# design.net
KiCad netlist of a schematic drawn in Altium Designer
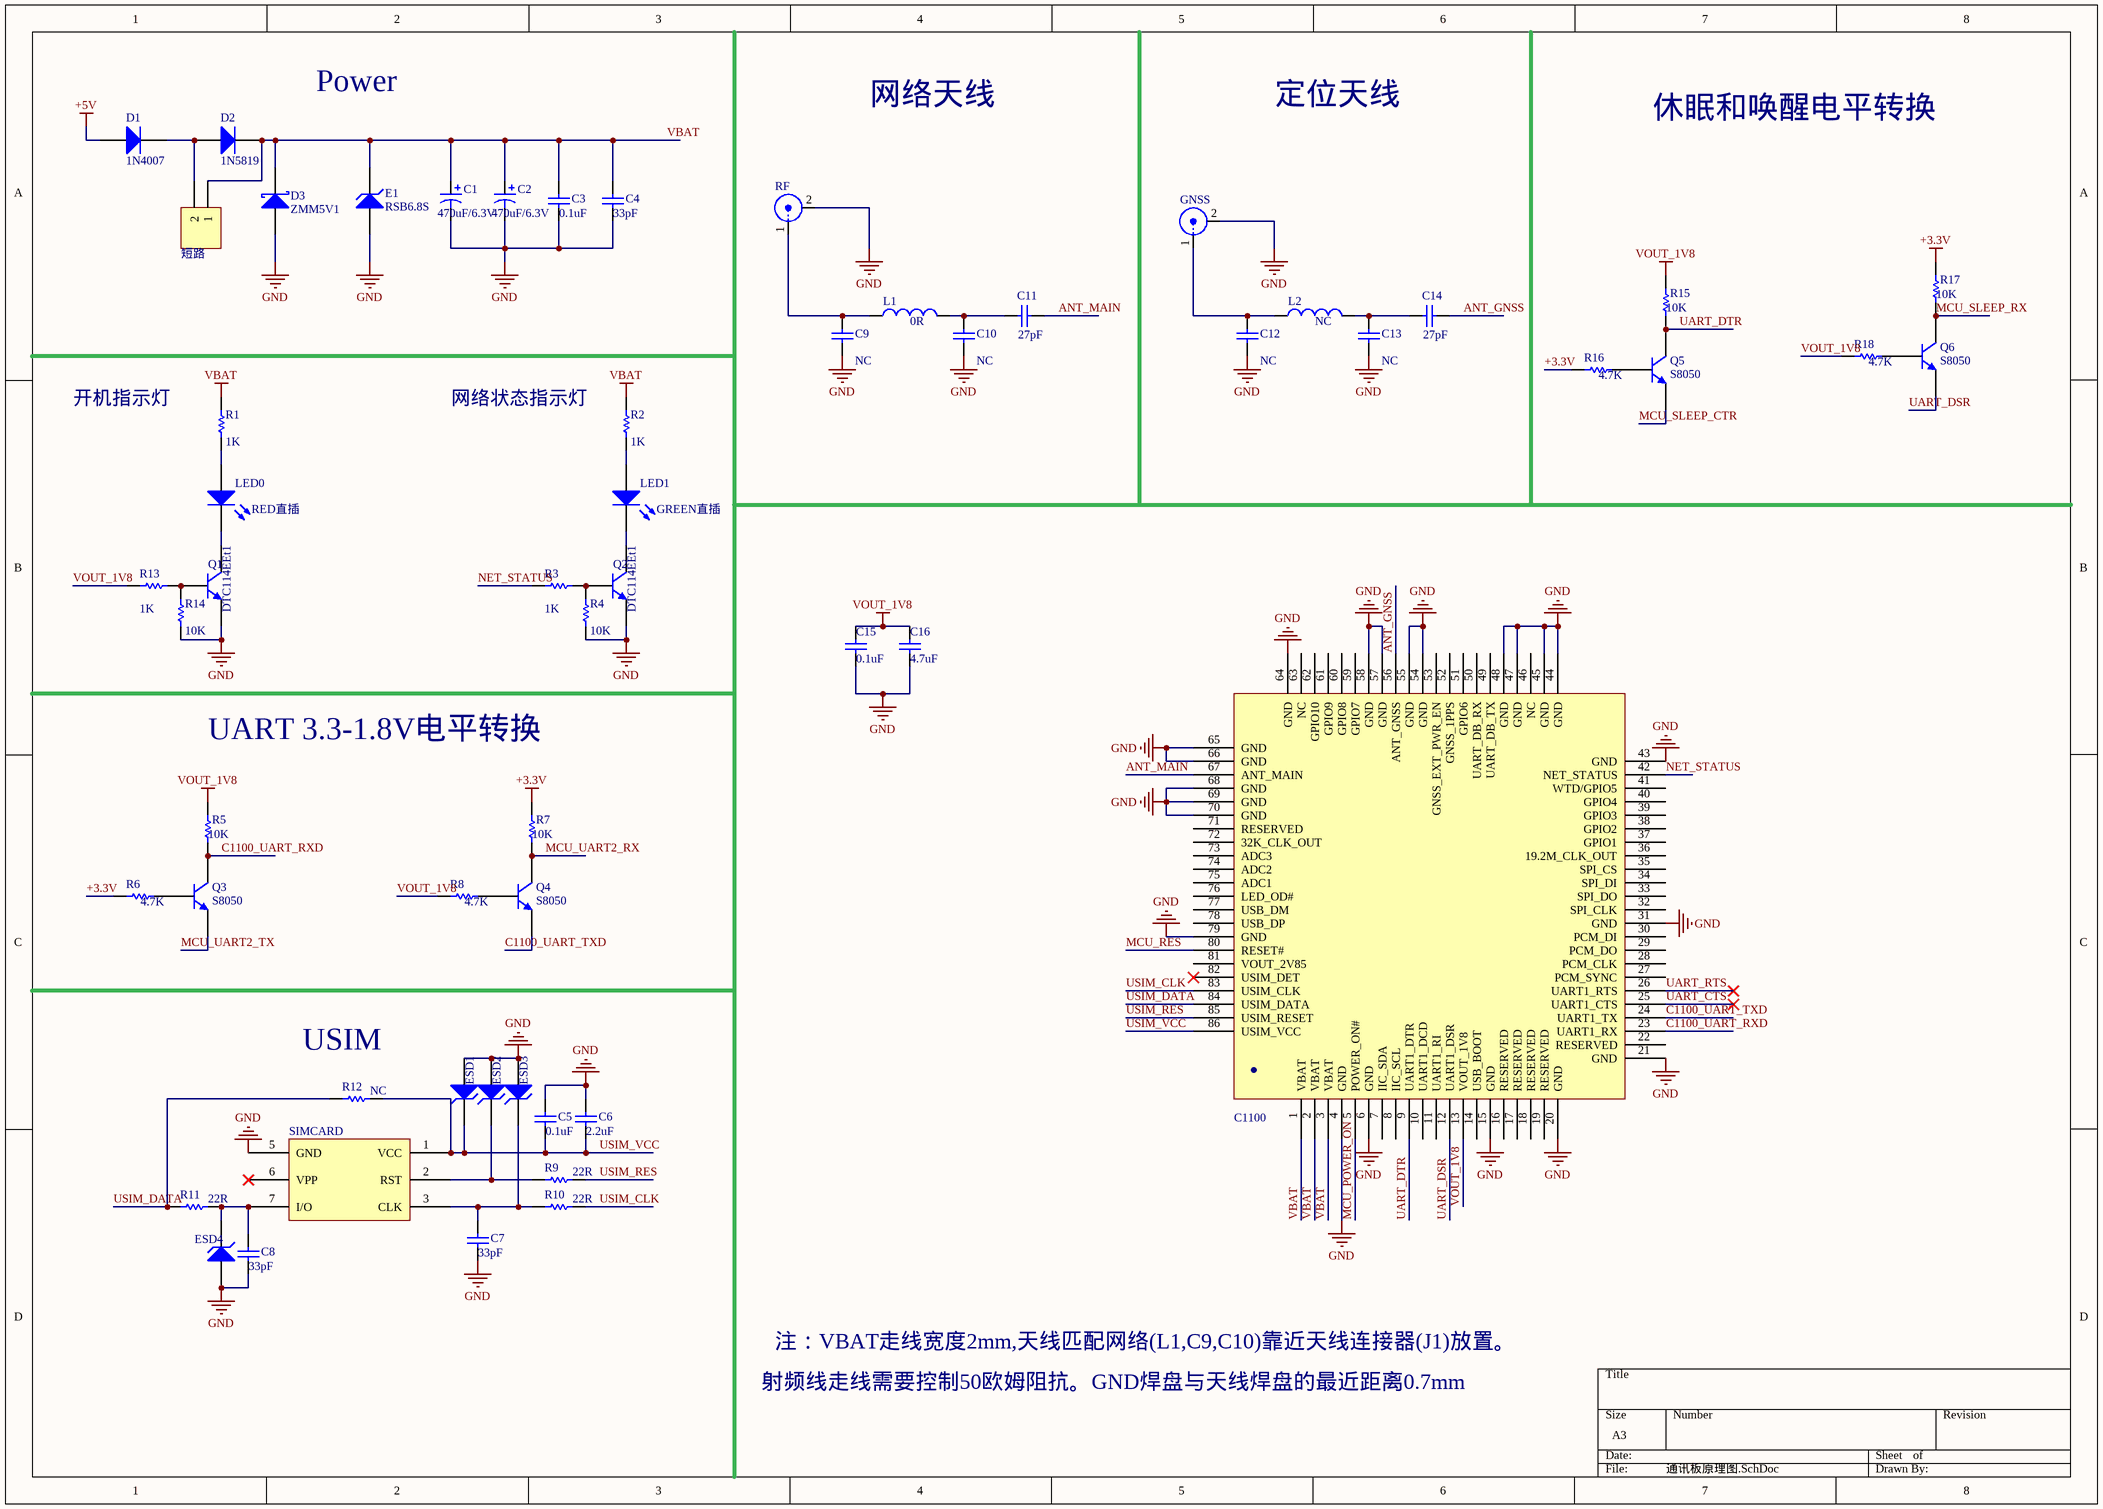
[diagram p0: 通讯板原理图.SchDoc]

(export (version "E")
  (design (tool "Eeschema 10.0.6"))
  (components
    (comp (ref "C1")
      (value "470uF/6.3V")
      (footprint "钽电容(D)")
      (description "Polarized Capacitor (Radial)")
      (fields (field (name "Comment") "477L") (field (name "PUBLISHER") "Altium Limited"))
      (libsource (lib "Miscellaneous Devices") (part "Cap Pol1"))
    )
    (comp (ref "C2")
      (value "470uF/6.3V")
      (footprint "钽电容(D)")
      (description "Polarized Capacitor (Radial)")
      (fields (field (name "Comment") "477L") (field (name "PUBLISHER") "Altium Limited"))
      (libsource (lib "Miscellaneous Devices") (part "Cap Pol1"))
    )
    (comp (ref "C3")
      (value "0.1uF")
      (footprint "0805")
      (description "Capacitor")
      (fields (field (name "Comment") "104") (field (name "PUBLISHER") "Altium Limited"))
      (libsource (lib "Miscellaneous Devices") (part "Cap"))
    )
    (comp (ref "C4")
      (value "33pF")
      (footprint "0805")
      (description "Capacitor")
      (fields (field (name "Comment") "33") (field (name "PUBLISHER") "Altium Limited"))
      (libsource (lib "Miscellaneous Devices") (part "Cap"))
    )
    (comp (ref "C5")
      (value "0.1uF")
      (footprint "0805")
      (description "Capacitor")
      (fields (field (name "Comment") "104") (field (name "PUBLISHER") "Altium Limited"))
      (libsource (lib "Miscellaneous Devices") (part "Cap"))
    )
    (comp (ref "C6")
      (value "2.2uF")
      (footprint "0805")
      (description "Capacitor")
      (fields (field (name "Comment") "225") (field (name "PUBLISHER") "Altium Limited"))
      (libsource (lib "Miscellaneous Devices") (part "Cap"))
    )
    (comp (ref "C7")
      (value "33pF")
      (footprint "0805")
      (description "Capacitor")
      (fields (field (name "Comment") "33") (field (name "PUBLISHER") "Altium Limited"))
      (libsource (lib "Miscellaneous Devices") (part "Cap"))
    )
    (comp (ref "C8")
      (value "33pF")
      (footprint "0805")
      (description "Capacitor")
      (fields (field (name "Comment") "33") (field (name "PUBLISHER") "Altium Limited"))
      (libsource (lib "Miscellaneous Devices") (part "Cap"))
    )
    (comp (ref "C9")
      (value "NC")
      (footprint "0805")
      (description "Capacitor")
      (fields (field (name "PUBLISHER") "Altium Limited"))
      (libsource (lib "Miscellaneous Devices") (part "Cap"))
    )
    (comp (ref "C10")
      (value "NC")
      (footprint "0805")
      (description "Capacitor")
      (fields (field (name "PUBLISHER") "Altium Limited"))
      (libsource (lib "Miscellaneous Devices") (part "Cap"))
    )
    (comp (ref "C11")
      (value "27pF")
      (footprint "0805")
      (description "Capacitor")
      (fields (field (name "Comment") "27") (field (name "PUBLISHER") "Altium Limited"))
      (libsource (lib "Miscellaneous Devices") (part "Cap"))
    )
    (comp (ref "C12")
      (value "NC")
      (footprint "0805")
      (description "Capacitor")
      (fields (field (name "PUBLISHER") "Altium Limited"))
      (libsource (lib "Miscellaneous Devices") (part "Cap"))
    )
    (comp (ref "C13")
      (value "NC")
      (footprint "0805")
      (description "Capacitor")
      (fields (field (name "PUBLISHER") "Altium Limited"))
      (libsource (lib "Miscellaneous Devices") (part "Cap"))
    )
    (comp (ref "C14")
      (value "27pF")
      (footprint "0805")
      (description "Capacitor")
      (fields (field (name "Comment") "27") (field (name "PUBLISHER") "Altium Limited"))
      (libsource (lib "Miscellaneous Devices") (part "Cap"))
    )
    (comp (ref "C15")
      (value "0.1uF")
      (footprint "0805")
      (description "Capacitor")
      (fields (field (name "Comment") "104") (field (name "PUBLISHER") "Altium Limited"))
      (libsource (lib "Miscellaneous Devices") (part "Cap"))
    )
    (comp (ref "C16")
      (value "4.7uF")
      (footprint "0805")
      (description "Capacitor")
      (fields (field (name "Comment") "475") (field (name "PUBLISHER") "Altium Limited"))
      (libsource (lib "Miscellaneous Devices") (part "Cap"))
    )
    (comp (ref "C1100") (value "C1100") (footprint "C1100") (libsource (lib "Schlib1") (part "C1100")))
    (comp (ref "D1")
      (value "1N4007")
      (footprint "M7")
      (description "1 Amp General Purpose Rectifier")
      (fields (field (name "PUBLISHER") "Altium Limited"))
      (libsource (lib "Miscellaneous Devices") (part "Diode 1N4007"))
    )
    (comp (ref "D2")
      (value "1N5819")
      (footprint "M7")
      (description "3 Amp General Purpose Rectifier")
      (fields (field (name "PUBLISHER") "Altium Limited"))
      (libsource (lib "Miscellaneous Devices") (part "Diode 1N5402"))
    )
    (comp (ref "D3")
      (value "ZMM5V1")
      (footprint "ZMM5V1")
      (description "Schottky Rectifier")
      (fields (field (name "PUBLISHER") "Altium Limited"))
      (libsource (lib "Miscellaneous Devices") (part "Diode 10TQ035"))
    )
    (comp (ref "E1")
      (value "RSB6.8S")
      (footprint "0603")
      (description "Zener Diode")
      (fields (field (name "PUBLISHER") "Altium Limited"))
      (libsource (lib "Miscellaneous Devices") (part "D Zener"))
    )
    (comp (ref "ESD1")
      (value "SZESD7361HT1G")
      (footprint "0603")
      (description "Zener Diode")
      (fields (field (name "PUBLISHER") "Altium Limited"))
      (libsource (lib "Miscellaneous Devices") (part "D Zener"))
    )
    (comp (ref "ESD2")
      (value "SZESD7361HT1G")
      (footprint "0603")
      (description "Zener Diode")
      (fields (field (name "PUBLISHER") "Altium Limited"))
      (libsource (lib "Miscellaneous Devices") (part "D Zener"))
    )
    (comp (ref "ESD3")
      (value "SZESD7361HT1G")
      (footprint "0603")
      (description "Zener Diode")
      (fields (field (name "PUBLISHER") "Altium Limited"))
      (libsource (lib "Miscellaneous Devices") (part "D Zener"))
    )
    (comp (ref "ESD4")
      (value "SZESD7361HT1G")
      (footprint "0603")
      (description "Zener Diode")
      (fields (field (name "PUBLISHER") "Altium Limited"))
      (libsource (lib "Miscellaneous Devices") (part "D Zener"))
    )
    (comp (ref "GNSS")
      (value "IPX")
      (footprint "IPX")
      (description "SMB Straight Connector")
      (fields (field (name "PUBLISHER") "Altium Limited"))
      (libsource (lib "Miscellaneous Connectors") (part "SMB"))
    )
    (comp (ref "L1")
      (value "0R")
      (footprint "0805")
      (description "Inductor")
      (fields (field (name "PUBLISHER") "Altium Limited"))
      (libsource (lib "Miscellaneous Devices") (part "Inductor"))
    )
    (comp (ref "L2")
      (value "NC")
      (footprint "0805")
      (description "Inductor")
      (fields (field (name "PUBLISHER") "Altium Limited"))
      (libsource (lib "Miscellaneous Devices") (part "Inductor"))
    )
    (comp (ref "LED0")
      (value "RED直插")
      (footprint "LED")
      (description "Typical INFRARED GaAs LED")
      (fields (field (name "PUBLISHER") "Altium Limited"))
      (libsource (lib "Miscellaneous Devices") (part "LED0"))
    )
    (comp (ref "LED1")
      (value "GREEN直插")
      (footprint "LED")
      (description "Typical INFRARED GaAs LED")
      (fields (field (name "PUBLISHER") "Altium Limited"))
      (libsource (lib "Miscellaneous Devices") (part "LED0"))
    )
    (comp (ref "Q1")
      (value "DTC114EEt1")
      (footprint "DTC114EEt1")
      (description "NPN Bipolar Transistor")
      (fields (field (name "PUBLISHER") "Altium Limited"))
      (libsource (lib "Miscellaneous Devices") (part "NPN"))
    )
    (comp (ref "Q2")
      (value "DTC114EEt1")
      (footprint "DTC114EEt1")
      (description "NPN Bipolar Transistor")
      (fields (field (name "PUBLISHER") "Altium Limited"))
      (libsource (lib "Miscellaneous Devices") (part "NPN"))
    )
    (comp (ref "Q3")
      (value "S8050")
      (footprint "NPN")
      (description "NPN Bipolar Transistor")
      (fields (field (name "PUBLISHER") "Altium Limited"))
      (libsource (lib "Miscellaneous Devices") (part "NPN"))
    )
    (comp (ref "Q4")
      (value "S8050")
      (footprint "NPN")
      (description "NPN Bipolar Transistor")
      (fields (field (name "PUBLISHER") "Altium Limited"))
      (libsource (lib "Miscellaneous Devices") (part "NPN"))
    )
    (comp (ref "Q5")
      (value "S8050")
      (footprint "NPN")
      (description "NPN Bipolar Transistor")
      (fields (field (name "PUBLISHER") "Altium Limited"))
      (libsource (lib "Miscellaneous Devices") (part "NPN"))
    )
    (comp (ref "Q6")
      (value "S8050")
      (footprint "NPN")
      (description "NPN Bipolar Transistor")
      (fields (field (name "PUBLISHER") "Altium Limited"))
      (libsource (lib "Miscellaneous Devices") (part "NPN"))
    )
    (comp (ref "R1")
      (value "1K")
      (footprint "0805")
      (description "Resistor")
      (fields (field (name "PUBLISHER") "Altium Limited"))
      (libsource (lib "Miscellaneous Devices") (part "Res1"))
    )
    (comp (ref "R2")
      (value "1K")
      (footprint "0805")
      (description "Resistor")
      (fields (field (name "PUBLISHER") "Altium Limited"))
      (libsource (lib "Miscellaneous Devices") (part "Res1"))
    )
    (comp (ref "R3")
      (value "1K")
      (footprint "0805")
      (description "Resistor")
      (fields (field (name "PUBLISHER") "Altium Limited"))
      (libsource (lib "Miscellaneous Devices") (part "Res1"))
    )
    (comp (ref "R4")
      (value "10K")
      (footprint "0805")
      (description "Resistor")
      (fields (field (name "PUBLISHER") "Altium Limited"))
      (libsource (lib "Miscellaneous Devices") (part "Res1"))
    )
    (comp (ref "R5")
      (value "10K")
      (footprint "0805")
      (description "Resistor")
      (fields (field (name "PUBLISHER") "Altium Limited"))
      (libsource (lib "Miscellaneous Devices") (part "Res1"))
    )
    (comp (ref "R6")
      (value "4.7K")
      (footprint "0805")
      (description "Resistor")
      (fields (field (name "PUBLISHER") "Altium Limited"))
      (libsource (lib "Miscellaneous Devices") (part "Res1"))
    )
    (comp (ref "R7")
      (value "10K")
      (footprint "0805")
      (description "Resistor")
      (fields (field (name "PUBLISHER") "Altium Limited"))
      (libsource (lib "Miscellaneous Devices") (part "Res1"))
    )
    (comp (ref "R8")
      (value "4.7K")
      (footprint "0805")
      (description "Resistor")
      (fields (field (name "PUBLISHER") "Altium Limited"))
      (libsource (lib "Miscellaneous Devices") (part "Res1"))
    )
    (comp (ref "R9")
      (value "22R")
      (footprint "0805")
      (description "Resistor")
      (fields (field (name "PUBLISHER") "Altium Limited"))
      (libsource (lib "Miscellaneous Devices") (part "Res1"))
    )
    (comp (ref "R10")
      (value "22R")
      (footprint "0805")
      (description "Resistor")
      (fields (field (name "PUBLISHER") "Altium Limited"))
      (libsource (lib "Miscellaneous Devices") (part "Res1"))
    )
    (comp (ref "R11")
      (value "22R")
      (footprint "0805")
      (description "Resistor")
      (fields (field (name "PUBLISHER") "Altium Limited"))
      (libsource (lib "Miscellaneous Devices") (part "Res1"))
    )
    (comp (ref "R12")
      (value "NC")
      (footprint "0805")
      (description "Resistor")
      (fields (field (name "PUBLISHER") "Altium Limited"))
      (libsource (lib "Miscellaneous Devices") (part "Res1"))
    )
    (comp (ref "R13")
      (value "1K")
      (footprint "0805")
      (description "Resistor")
      (fields (field (name "PUBLISHER") "Altium Limited"))
      (libsource (lib "Miscellaneous Devices") (part "Res1"))
    )
    (comp (ref "R14")
      (value "10K")
      (footprint "0805")
      (description "Resistor")
      (fields (field (name "PUBLISHER") "Altium Limited"))
      (libsource (lib "Miscellaneous Devices") (part "Res1"))
    )
    (comp (ref "R15")
      (value "10K")
      (footprint "0805")
      (description "Resistor")
      (fields (field (name "PUBLISHER") "Altium Limited"))
      (libsource (lib "Miscellaneous Devices") (part "Res1"))
    )
    (comp (ref "R16")
      (value "4.7K")
      (footprint "0805")
      (description "Resistor")
      (fields (field (name "PUBLISHER") "Altium Limited"))
      (libsource (lib "Miscellaneous Devices") (part "Res1"))
    )
    (comp (ref "R17")
      (value "10K")
      (footprint "0805")
      (description "Resistor")
      (fields (field (name "PUBLISHER") "Altium Limited"))
      (libsource (lib "Miscellaneous Devices") (part "Res1"))
    )
    (comp (ref "R18")
      (value "4.7K")
      (footprint "0805")
      (description "Resistor")
      (fields (field (name "PUBLISHER") "Altium Limited"))
      (libsource (lib "Miscellaneous Devices") (part "Res1"))
    )
    (comp (ref "RF")
      (value "SMA")
      (footprint "SMA-2")
      (description "SMB Straight Connector")
      (fields (field (name "PUBLISHER") "Altium Limited"))
      (libsource (lib "Miscellaneous Connectors") (part "SMB"))
    )
    (comp (ref "SIMCARD")
      (value "SIM-ACARD")
      (footprint "SIMCARD")
      (libsource (lib "Schlib1") (part "SIMCARD"))
    )
    (comp (ref "短路")
      (value "Header 2")
      (footprint "HEDX2")
      (description "Header, 2-Pin")
      (fields (field (name "PUBLISHER") "Altium Limited"))
      (libsource (lib "Miscellaneous Connectors") (part "Header 2"))
    )
  )
  (nets
    (net (code "1") (name "+3.3V") (class "Default")
      (node (ref "R16") (pin "1") (pinfunction "1_1") (pintype "passive"))
      (node (ref "R17") (pin "2") (pinfunction "2_2") (pintype "passive"))
      (node (ref "R6") (pin "1") (pinfunction "1_1") (pintype "passive"))
      (node (ref "R7") (pin "2") (pinfunction "2_2") (pintype "passive"))
    )
    (net (code "2") (name "+5V") (class "Default")
      (node (ref "D1") (pin "1") (pinfunction "A_1") (pintype "passive"))
    )
    (net (code "3") (name "/ANT_GNSS") (class "Default")
      (node (ref "C1100") (pin "56") (pinfunction "ANT_GNSS_56") (pintype "passive"))
      (node (ref "C14") (pin "2") (pinfunction "2_2") (pintype "passive"))
    )
    (net (code "4") (name "/ANT_MAIN") (class "Default")
      (node (ref "C11") (pin "2") (pinfunction "2_2") (pintype "passive"))
      (node (ref "C1100") (pin "67") (pinfunction "ANT_MAIN_67") (pintype "passive"))
    )
    (net (code "5") (name "/C1100_UART_RXD") (class "Default")
      (node (ref "C1100") (pin "23") (pinfunction "UART1_RX_23") (pintype "passive"))
      (node (ref "Q3") (pin "3") (pinfunction "C_3") (pintype "passive"))
      (node (ref "R5") (pin "1") (pinfunction "1_1") (pintype "passive"))
    )
    (net (code "6") (name "/C1100_UART_TXD") (class "Default")
      (node (ref "C1100") (pin "24") (pinfunction "UART1_TX_24") (pintype "passive"))
      (node (ref "Q4") (pin "2") (pinfunction "E_2") (pintype "passive"))
    )
    (net (code "7") (name "/MCU_POWER_ON") (class "Default")
      (node (ref "C1100") (pin "5") (pinfunction "POWER_ON#_5") (pintype "passive"))
    )
    (net (code "8") (name "/MCU_RES") (class "Default")
      (node (ref "C1100") (pin "80") (pinfunction "RESET#_80") (pintype "passive"))
    )
    (net (code "9") (name "/MCU_SLEEP_CTR") (class "Default")
      (node (ref "Q5") (pin "2") (pinfunction "E_2") (pintype "passive"))
    )
    (net (code "10") (name "/MCU_SLEEP_RX") (class "Default")
      (node (ref "Q6") (pin "3") (pinfunction "C_3") (pintype "passive"))
      (node (ref "R17") (pin "1") (pinfunction "1_1") (pintype "passive"))
    )
    (net (code "11") (name "/MCU_UART2_RX") (class "Default")
      (node (ref "Q4") (pin "3") (pinfunction "C_3") (pintype "passive"))
      (node (ref "R7") (pin "1") (pinfunction "1_1") (pintype "passive"))
    )
    (net (code "12") (name "/MCU_UART2_TX") (class "Default")
      (node (ref "Q3") (pin "2") (pinfunction "E_2") (pintype "passive"))
    )
    (net (code "13") (name "/NET_STATUS") (class "Default")
      (node (ref "C1100") (pin "42") (pinfunction "NET_STATUS_42") (pintype "passive"))
      (node (ref "R3") (pin "1") (pinfunction "1_1") (pintype "passive"))
    )
    (net (code "14") (name "/UART_CTS") (class "Default")
      (node (ref "C1100") (pin "25") (pinfunction "UART1_CTS_25") (pintype "passive+no_connect"))
    )
    (net (code "15") (name "/UART_DSR") (class "Default")
      (node (ref "C1100") (pin "12") (pinfunction "UART1_DSR_12") (pintype "passive"))
      (node (ref "Q6") (pin "2") (pinfunction "E_2") (pintype "passive"))
    )
    (net (code "16") (name "/UART_DTR") (class "Default")
      (node (ref "C1100") (pin "9") (pinfunction "UART1_DTR_9") (pintype "passive"))
      (node (ref "Q5") (pin "3") (pinfunction "C_3") (pintype "passive"))
      (node (ref "R15") (pin "1") (pinfunction "1_1") (pintype "passive"))
    )
    (net (code "17") (name "/UART_RTS") (class "Default")
      (node (ref "C1100") (pin "26") (pinfunction "UART1_RTS_26") (pintype "passive+no_connect"))
    )
    (net (code "18") (name "/USIM_CLK") (class "Default")
      (node (ref "C1100") (pin "83") (pinfunction "USIM_CLK_83") (pintype "passive"))
      (node (ref "R10") (pin "2") (pinfunction "2_2") (pintype "passive"))
    )
    (net (code "19") (name "/USIM_DATA") (class "Default")
      (node (ref "C1100") (pin "84") (pinfunction "USIM_DATA_84") (pintype "passive"))
      (node (ref "R11") (pin "1") (pinfunction "1_1") (pintype "passive"))
      (node (ref "R12") (pin "1") (pinfunction "1_1") (pintype "passive"))
    )
    (net (code "20") (name "/USIM_RES") (class "Default")
      (node (ref "C1100") (pin "85") (pinfunction "USIM_RESET_85") (pintype "passive"))
      (node (ref "R9") (pin "2") (pinfunction "2_2") (pintype "passive"))
    )
    (net (code "21") (name "/USIM_VCC") (class "Default")
      (node (ref "C1100") (pin "86") (pinfunction "USIM_VCC_86") (pintype "passive"))
      (node (ref "C5") (pin "1") (pinfunction "1_1") (pintype "passive"))
      (node (ref "C6") (pin "1") (pinfunction "1_1") (pintype "passive"))
      (node (ref "ESD1") (pin "2") (pinfunction "K_2") (pintype "passive"))
      (node (ref "R12") (pin "2") (pinfunction "2_2") (pintype "passive"))
      (node (ref "SIMCARD") (pin "1") (pinfunction "VCC_1") (pintype "passive"))
    )
    (net (code "22") (name "GND") (class "Default")
      (node (ref "C1") (pin "2") (pinfunction "2_2") (pintype "passive"))
      (node (ref "C10") (pin "1") (pinfunction "1_1") (pintype "passive"))
      (node (ref "C1100") (pin "15") (pinfunction "GND_15") (pintype "passive"))
      (node (ref "C1100") (pin "20") (pinfunction "GND_20") (pintype "passive"))
      (node (ref "C1100") (pin "21") (pinfunction "GND_21") (pintype "passive"))
      (node (ref "C1100") (pin "31") (pinfunction "GND_31") (pintype "passive"))
      (node (ref "C1100") (pin "4") (pinfunction "GND_4") (pintype "passive"))
      (node (ref "C1100") (pin "43") (pinfunction "GND_43") (pintype "passive"))
      (node (ref "C1100") (pin "44") (pinfunction "GND_44") (pintype "passive"))
      (node (ref "C1100") (pin "45") (pinfunction "GND_45") (pintype "passive"))
      (node (ref "C1100") (pin "47") (pinfunction "GND_47") (pintype "passive"))
      (node (ref "C1100") (pin "48") (pinfunction "GND_48") (pintype "passive"))
      (node (ref "C1100") (pin "54") (pinfunction "GND_54") (pintype "passive"))
      (node (ref "C1100") (pin "55") (pinfunction "GND_55") (pintype "passive"))
      (node (ref "C1100") (pin "57") (pinfunction "GND_57") (pintype "passive"))
      (node (ref "C1100") (pin "58") (pinfunction "GND_58") (pintype "passive"))
      (node (ref "C1100") (pin "6") (pinfunction "GND_6") (pintype "passive"))
      (node (ref "C1100") (pin "64") (pinfunction "GND_64") (pintype "passive"))
      (node (ref "C1100") (pin "65") (pinfunction "GND_65") (pintype "passive"))
      (node (ref "C1100") (pin "66") (pinfunction "GND_66") (pintype "passive"))
      (node (ref "C1100") (pin "68") (pinfunction "GND_68") (pintype "passive"))
      (node (ref "C1100") (pin "69") (pinfunction "GND_69") (pintype "passive"))
      (node (ref "C1100") (pin "70") (pinfunction "GND_70") (pintype "passive"))
      (node (ref "C1100") (pin "79") (pinfunction "GND_79") (pintype "passive"))
      (node (ref "C12") (pin "1") (pinfunction "1_1") (pintype "passive"))
      (node (ref "C13") (pin "1") (pinfunction "1_1") (pintype "passive"))
      (node (ref "C15") (pin "1") (pinfunction "1_1") (pintype "passive"))
      (node (ref "C16") (pin "1") (pinfunction "1_1") (pintype "passive"))
      (node (ref "C2") (pin "2") (pinfunction "2_2") (pintype "passive"))
      (node (ref "C3") (pin "2") (pinfunction "2_2") (pintype "passive"))
      (node (ref "C4") (pin "2") (pinfunction "2_2") (pintype "passive"))
      (node (ref "C5") (pin "2") (pinfunction "2_2") (pintype "passive"))
      (node (ref "C6") (pin "2") (pinfunction "2_2") (pintype "passive"))
      (node (ref "C7") (pin "1") (pinfunction "1_1") (pintype "passive"))
      (node (ref "C8") (pin "1") (pinfunction "1_1") (pintype "passive"))
      (node (ref "C9") (pin "1") (pinfunction "1_1") (pintype "passive"))
      (node (ref "D3") (pin "1") (pinfunction "A_1") (pintype "passive"))
      (node (ref "E1") (pin "1") (pinfunction "A_1") (pintype "passive"))
      (node (ref "ESD1") (pin "1") (pinfunction "A_1") (pintype "passive"))
      (node (ref "ESD2") (pin "1") (pinfunction "A_1") (pintype "passive"))
      (node (ref "ESD3") (pin "1") (pinfunction "A_1") (pintype "passive"))
      (node (ref "ESD4") (pin "1") (pinfunction "A_1") (pintype "passive"))
      (node (ref "GNSS") (pin "2") (pinfunction "Y_2") (pintype "passive"))
      (node (ref "Q1") (pin "2") (pinfunction "E_2") (pintype "passive"))
      (node (ref "Q2") (pin "2") (pinfunction "E_2") (pintype "passive"))
      (node (ref "R14") (pin "1") (pinfunction "1_1") (pintype "passive"))
      (node (ref "R4") (pin "1") (pinfunction "1_1") (pintype "passive"))
      (node (ref "RF") (pin "2") (pinfunction "Y_2") (pintype "passive"))
      (node (ref "SIMCARD") (pin "5") (pinfunction "GND_5") (pintype "passive"))
    )
    (net (code "23") (name "Net-(C10-Pad2)") (class "Default")
      (node (ref "C10") (pin "2") (pinfunction "2_2") (pintype "passive"))
      (node (ref "C11") (pin "1") (pinfunction "1_1") (pintype "passive"))
      (node (ref "L1") (pin "2") (pinfunction "2_2") (pintype "passive"))
    )
    (net (code "24") (name "Net-(C13-Pad2)") (class "Default")
      (node (ref "C13") (pin "2") (pinfunction "2_2") (pintype "passive"))
      (node (ref "C14") (pin "1") (pinfunction "1_1") (pintype "passive"))
      (node (ref "L2") (pin "2") (pinfunction "2_2") (pintype "passive"))
    )
    (net (code "25") (name "Net-(D1-K)") (class "Default")
      (node (ref "D1") (pin "2") (pinfunction "K_2") (pintype "passive"))
      (node (ref "D2") (pin "1") (pinfunction "A_1") (pintype "passive"))
      (node (ref "短路") (pin "2") (pinfunction "2_2") (pintype "passive"))
    )
    (net (code "26") (name "Net-(ESD2-K)") (class "Default")
      (node (ref "ESD2") (pin "2") (pinfunction "K_2") (pintype "passive"))
      (node (ref "R9") (pin "1") (pinfunction "1_1") (pintype "passive"))
      (node (ref "SIMCARD") (pin "2") (pinfunction "RST_2") (pintype "passive"))
    )
    (net (code "27") (name "Net-(ESD3-K)") (class "Default")
      (node (ref "C7") (pin "2") (pinfunction "2_2") (pintype "passive"))
      (node (ref "ESD3") (pin "2") (pinfunction "K_2") (pintype "passive"))
      (node (ref "R10") (pin "1") (pinfunction "1_1") (pintype "passive"))
      (node (ref "SIMCARD") (pin "3") (pinfunction "CLK_3") (pintype "passive"))
    )
    (net (code "28") (name "Net-(ESD4-K)") (class "Default")
      (node (ref "C8") (pin "2") (pinfunction "2_2") (pintype "passive"))
      (node (ref "ESD4") (pin "2") (pinfunction "K_2") (pintype "passive"))
      (node (ref "R11") (pin "2") (pinfunction "2_2") (pintype "passive"))
      (node (ref "SIMCARD") (pin "7") (pinfunction "I/O_7") (pintype "passive"))
    )
    (net (code "29") (name "Net-(GNSS-X)") (class "Default")
      (node (ref "C12") (pin "2") (pinfunction "2_2") (pintype "passive"))
      (node (ref "GNSS") (pin "1") (pinfunction "X_1") (pintype "passive"))
      (node (ref "L2") (pin "1") (pinfunction "1_1") (pintype "passive"))
    )
    (net (code "30") (name "Net-(LED0-A)") (class "Default")
      (node (ref "LED0") (pin "1") (pinfunction "A_1") (pintype "passive"))
      (node (ref "R1") (pin "1") (pinfunction "1_1") (pintype "passive"))
    )
    (net (code "31") (name "Net-(LED0-K)") (class "Default")
      (node (ref "LED0") (pin "2") (pinfunction "K_2") (pintype "passive"))
      (node (ref "Q1") (pin "3") (pinfunction "C_3") (pintype "passive"))
    )
    (net (code "32") (name "Net-(LED1-A)") (class "Default")
      (node (ref "LED1") (pin "1") (pinfunction "A_1") (pintype "passive"))
      (node (ref "R2") (pin "1") (pinfunction "1_1") (pintype "passive"))
    )
    (net (code "33") (name "Net-(LED1-K)") (class "Default")
      (node (ref "LED1") (pin "2") (pinfunction "K_2") (pintype "passive"))
      (node (ref "Q2") (pin "3") (pinfunction "C_3") (pintype "passive"))
    )
    (net (code "34") (name "Net-(Q1-B)") (class "Default")
      (node (ref "Q1") (pin "1") (pinfunction "B_1") (pintype "passive"))
      (node (ref "R13") (pin "2") (pinfunction "2_2") (pintype "passive"))
      (node (ref "R14") (pin "2") (pinfunction "2_2") (pintype "passive"))
    )
    (net (code "35") (name "Net-(Q2-B)") (class "Default")
      (node (ref "Q2") (pin "1") (pinfunction "B_1") (pintype "passive"))
      (node (ref "R3") (pin "2") (pinfunction "2_2") (pintype "passive"))
      (node (ref "R4") (pin "2") (pinfunction "2_2") (pintype "passive"))
    )
    (net (code "36") (name "Net-(Q3-B)") (class "Default")
      (node (ref "Q3") (pin "1") (pinfunction "B_1") (pintype "passive"))
      (node (ref "R6") (pin "2") (pinfunction "2_2") (pintype "passive"))
    )
    (net (code "37") (name "Net-(Q4-B)") (class "Default")
      (node (ref "Q4") (pin "1") (pinfunction "B_1") (pintype "passive"))
      (node (ref "R8") (pin "2") (pinfunction "2_2") (pintype "passive"))
    )
    (net (code "38") (name "Net-(Q5-B)") (class "Default")
      (node (ref "Q5") (pin "1") (pinfunction "B_1") (pintype "passive"))
      (node (ref "R16") (pin "2") (pinfunction "2_2") (pintype "passive"))
    )
    (net (code "39") (name "Net-(Q6-B)") (class "Default")
      (node (ref "Q6") (pin "1") (pinfunction "B_1") (pintype "passive"))
      (node (ref "R18") (pin "2") (pinfunction "2_2") (pintype "passive"))
    )
    (net (code "40") (name "Net-(RF-X)") (class "Default")
      (node (ref "C9") (pin "2") (pinfunction "2_2") (pintype "passive"))
      (node (ref "L1") (pin "1") (pinfunction "1_1") (pintype "passive"))
      (node (ref "RF") (pin "1") (pinfunction "X_1") (pintype "passive"))
    )
    (net (code "41") (name "VBAT") (class "Default")
      (node (ref "C1") (pin "1") (pinfunction "1_1") (pintype "passive"))
      (node (ref "C1100") (pin "1") (pinfunction "VBAT_1") (pintype "passive"))
      (node (ref "C1100") (pin "2") (pinfunction "VBAT_2") (pintype "passive"))
      (node (ref "C1100") (pin "3") (pinfunction "VBAT_3") (pintype "passive"))
      (node (ref "C2") (pin "1") (pinfunction "1_1") (pintype "passive"))
      (node (ref "C3") (pin "1") (pinfunction "1_1") (pintype "passive"))
      (node (ref "C4") (pin "1") (pinfunction "1_1") (pintype "passive"))
      (node (ref "D2") (pin "2") (pinfunction "K_2") (pintype "passive"))
      (node (ref "D3") (pin "2") (pinfunction "K_2") (pintype "passive"))
      (node (ref "E1") (pin "2") (pinfunction "K_2") (pintype "passive"))
      (node (ref "R1") (pin "2") (pinfunction "2_2") (pintype "passive"))
      (node (ref "R2") (pin "2") (pinfunction "2_2") (pintype "passive"))
      (node (ref "短路") (pin "1") (pinfunction "1_1") (pintype "passive"))
    )
    (net (code "42") (name "VOUT_1V8") (class "Default")
      (node (ref "C1100") (pin "13") (pinfunction "VOUT_1V8_13") (pintype "passive"))
      (node (ref "C15") (pin "2") (pinfunction "2_2") (pintype "passive"))
      (node (ref "C16") (pin "2") (pinfunction "2_2") (pintype "passive"))
      (node (ref "R13") (pin "1") (pinfunction "1_1") (pintype "passive"))
      (node (ref "R15") (pin "2") (pinfunction "2_2") (pintype "passive"))
      (node (ref "R18") (pin "1") (pinfunction "1_1") (pintype "passive"))
      (node (ref "R5") (pin "2") (pinfunction "2_2") (pintype "passive"))
      (node (ref "R8") (pin "1") (pinfunction "1_1") (pintype "passive"))
    )
    (net (code "43") (name "unconnected-(C1100-19.2M_CLK_OUT-Pad36)") (class "Default")
      (node (ref "C1100") (pin "36") (pinfunction "19.2M_CLK_OUT_36") (pintype "passive"))
    )
    (net (code "44") (name "unconnected-(C1100-32K_CLK_OUT-Pad72)") (class "Default")
      (node (ref "C1100") (pin "72") (pinfunction "32K_CLK_OUT_72") (pintype "passive"))
    )
    (net (code "45") (name "unconnected-(C1100-ADC1-Pad75)") (class "Default")
      (node (ref "C1100") (pin "75") (pinfunction "ADC1_75") (pintype "passive"))
    )
    (net (code "46") (name "unconnected-(C1100-ADC2-Pad74)") (class "Default")
      (node (ref "C1100") (pin "74") (pinfunction "ADC2_74") (pintype "passive"))
    )
    (net (code "47") (name "unconnected-(C1100-ADC3-Pad73)") (class "Default")
      (node (ref "C1100") (pin "73") (pinfunction "ADC3_73") (pintype "passive"))
    )
    (net (code "48") (name "unconnected-(C1100-GNSS_1PPS-Pad52)") (class "Default")
      (node (ref "C1100") (pin "52") (pinfunction "GNSS_1PPS_52") (pintype "passive"))
    )
    (net (code "49") (name "unconnected-(C1100-GNSS_EXT_PWR_EN-Pad53)") (class "Default")
      (node (ref "C1100") (pin "53") (pinfunction "GNSS_EXT_PWR_EN_53") (pintype "passive"))
    )
    (net (code "50") (name "unconnected-(C1100-GPIO1-Pad37)") (class "Default")
      (node (ref "C1100") (pin "37") (pinfunction "GPIO1_37") (pintype "passive"))
    )
    (net (code "51") (name "unconnected-(C1100-GPIO2-Pad38)") (class "Default")
      (node (ref "C1100") (pin "38") (pinfunction "GPIO2_38") (pintype "passive"))
    )
    (net (code "52") (name "unconnected-(C1100-GPIO3-Pad39)") (class "Default")
      (node (ref "C1100") (pin "39") (pinfunction "GPIO3_39") (pintype "passive"))
    )
    (net (code "53") (name "unconnected-(C1100-GPIO4-Pad40)") (class "Default")
      (node (ref "C1100") (pin "40") (pinfunction "GPIO4_40") (pintype "passive"))
    )
    (net (code "54") (name "unconnected-(C1100-GPIO6-Pad51)") (class "Default")
      (node (ref "C1100") (pin "51") (pinfunction "GPIO6_51") (pintype "passive"))
    )
    (net (code "55") (name "unconnected-(C1100-GPIO7-Pad59)") (class "Default")
      (node (ref "C1100") (pin "59") (pinfunction "GPIO7_59") (pintype "passive"))
    )
    (net (code "56") (name "unconnected-(C1100-GPIO8-Pad60)") (class "Default")
      (node (ref "C1100") (pin "60") (pinfunction "GPIO8_60") (pintype "passive"))
    )
    (net (code "57") (name "unconnected-(C1100-GPIO9-Pad61)") (class "Default")
      (node (ref "C1100") (pin "61") (pinfunction "GPIO9_61") (pintype "passive"))
    )
    (net (code "58") (name "unconnected-(C1100-GPIO10-Pad62)") (class "Default")
      (node (ref "C1100") (pin "62") (pinfunction "GPIO10_62") (pintype "passive"))
    )
    (net (code "59") (name "unconnected-(C1100-IIC_SCL-Pad8)") (class "Default")
      (node (ref "C1100") (pin "8") (pinfunction "IIC_SCL_8") (pintype "passive"))
    )
    (net (code "60") (name "unconnected-(C1100-IIC_SDA-Pad7)") (class "Default")
      (node (ref "C1100") (pin "7") (pinfunction "IIC_SDA_7") (pintype "passive"))
    )
    (net (code "61") (name "unconnected-(C1100-LED_OD#-Pad76)") (class "Default")
      (node (ref "C1100") (pin "76") (pinfunction "LED_OD#_76") (pintype "passive"))
    )
    (net (code "62") (name "unconnected-(C1100-NC-Pad46)") (class "Default")
      (node (ref "C1100") (pin "46") (pinfunction "NC_46") (pintype "passive"))
    )
    (net (code "63") (name "unconnected-(C1100-NC-Pad63)") (class "Default")
      (node (ref "C1100") (pin "63") (pinfunction "NC_63") (pintype "passive"))
    )
    (net (code "64") (name "unconnected-(C1100-PCM_CLK-Pad28)") (class "Default")
      (node (ref "C1100") (pin "28") (pinfunction "PCM_CLK_28") (pintype "passive"))
    )
    (net (code "65") (name "unconnected-(C1100-PCM_DI-Pad30)") (class "Default")
      (node (ref "C1100") (pin "30") (pinfunction "PCM_DI_30") (pintype "passive"))
    )
    (net (code "66") (name "unconnected-(C1100-PCM_DO-Pad29)") (class "Default")
      (node (ref "C1100") (pin "29") (pinfunction "PCM_DO_29") (pintype "passive"))
    )
    (net (code "67") (name "unconnected-(C1100-PCM_SYNC-Pad27)") (class "Default")
      (node (ref "C1100") (pin "27") (pinfunction "PCM_SYNC_27") (pintype "passive"))
    )
    (net (code "68") (name "unconnected-(C1100-RESERVED-Pad16)") (class "Default")
      (node (ref "C1100") (pin "16") (pinfunction "RESERVED_16") (pintype "passive"))
    )
    (net (code "69") (name "unconnected-(C1100-RESERVED-Pad17)") (class "Default")
      (node (ref "C1100") (pin "17") (pinfunction "RESERVED_17") (pintype "passive"))
    )
    (net (code "70") (name "unconnected-(C1100-RESERVED-Pad18)") (class "Default")
      (node (ref "C1100") (pin "18") (pinfunction "RESERVED_18") (pintype "passive"))
    )
    (net (code "71") (name "unconnected-(C1100-RESERVED-Pad19)") (class "Default")
      (node (ref "C1100") (pin "19") (pinfunction "RESERVED_19") (pintype "passive"))
    )
    (net (code "72") (name "unconnected-(C1100-RESERVED-Pad22)") (class "Default")
      (node (ref "C1100") (pin "22") (pinfunction "RESERVED_22") (pintype "passive"))
    )
    (net (code "73") (name "unconnected-(C1100-RESERVED-Pad71)") (class "Default")
      (node (ref "C1100") (pin "71") (pinfunction "RESERVED_71") (pintype "passive"))
    )
    (net (code "74") (name "unconnected-(C1100-SPI_CLK-Pad32)") (class "Default")
      (node (ref "C1100") (pin "32") (pinfunction "SPI_CLK_32") (pintype "passive"))
    )
    (net (code "75") (name "unconnected-(C1100-SPI_CS-Pad35)") (class "Default")
      (node (ref "C1100") (pin "35") (pinfunction "SPI_CS_35") (pintype "passive"))
    )
    (net (code "76") (name "unconnected-(C1100-SPI_DI-Pad34)") (class "Default")
      (node (ref "C1100") (pin "34") (pinfunction "SPI_DI_34") (pintype "passive"))
    )
    (net (code "77") (name "unconnected-(C1100-SPI_DO-Pad33)") (class "Default")
      (node (ref "C1100") (pin "33") (pinfunction "SPI_DO_33") (pintype "passive"))
    )
    (net (code "78") (name "unconnected-(C1100-UART1_DCD-Pad10)") (class "Default")
      (node (ref "C1100") (pin "10") (pinfunction "UART1_DCD_10") (pintype "passive"))
    )
    (net (code "79") (name "unconnected-(C1100-UART1_RI-Pad11)") (class "Default")
      (node (ref "C1100") (pin "11") (pinfunction "UART1_RI_11") (pintype "passive"))
    )
    (net (code "80") (name "unconnected-(C1100-UART_DB_RX-Pad50)") (class "Default")
      (node (ref "C1100") (pin "50") (pinfunction "UART_DB_RX_50") (pintype "passive"))
    )
    (net (code "81") (name "unconnected-(C1100-UART_DB_TX-Pad49)") (class "Default")
      (node (ref "C1100") (pin "49") (pinfunction "UART_DB_TX_49") (pintype "passive"))
    )
    (net (code "82") (name "unconnected-(C1100-USB_BOOT-Pad14)") (class "Default")
      (node (ref "C1100") (pin "14") (pinfunction "USB_BOOT_14") (pintype "passive"))
    )
    (net (code "83") (name "unconnected-(C1100-USB_DM-Pad77)") (class "Default")
      (node (ref "C1100") (pin "77") (pinfunction "USB_DM_77") (pintype "passive"))
    )
    (net (code "84") (name "unconnected-(C1100-USB_DP-Pad78)") (class "Default")
      (node (ref "C1100") (pin "78") (pinfunction "USB_DP_78") (pintype "passive"))
    )
    (net (code "85") (name "unconnected-(C1100-USIM_DET-Pad82)") (class "Default")
      (node (ref "C1100") (pin "82") (pinfunction "USIM_DET_82") (pintype "passive+no_connect"))
    )
    (net (code "86") (name "unconnected-(C1100-VOUT_2V85-Pad81)") (class "Default")
      (node (ref "C1100") (pin "81") (pinfunction "VOUT_2V85_81") (pintype "passive"))
    )
    (net (code "87") (name "unconnected-(C1100-WTD{slash}GPIO5-Pad41)") (class "Default")
      (node (ref "C1100") (pin "41") (pinfunction "WTD/GPIO5_41") (pintype "passive"))
    )
    (net (code "88") (name "unconnected-(SIMCARD-VPP-Pad6)") (class "Default")
      (node (ref "SIMCARD") (pin "6") (pinfunction "VPP_6") (pintype "passive+no_connect"))
    )
  )
)
